# ESP32botV1.net
KiCad netlist of a schematic drawn in EAGLE
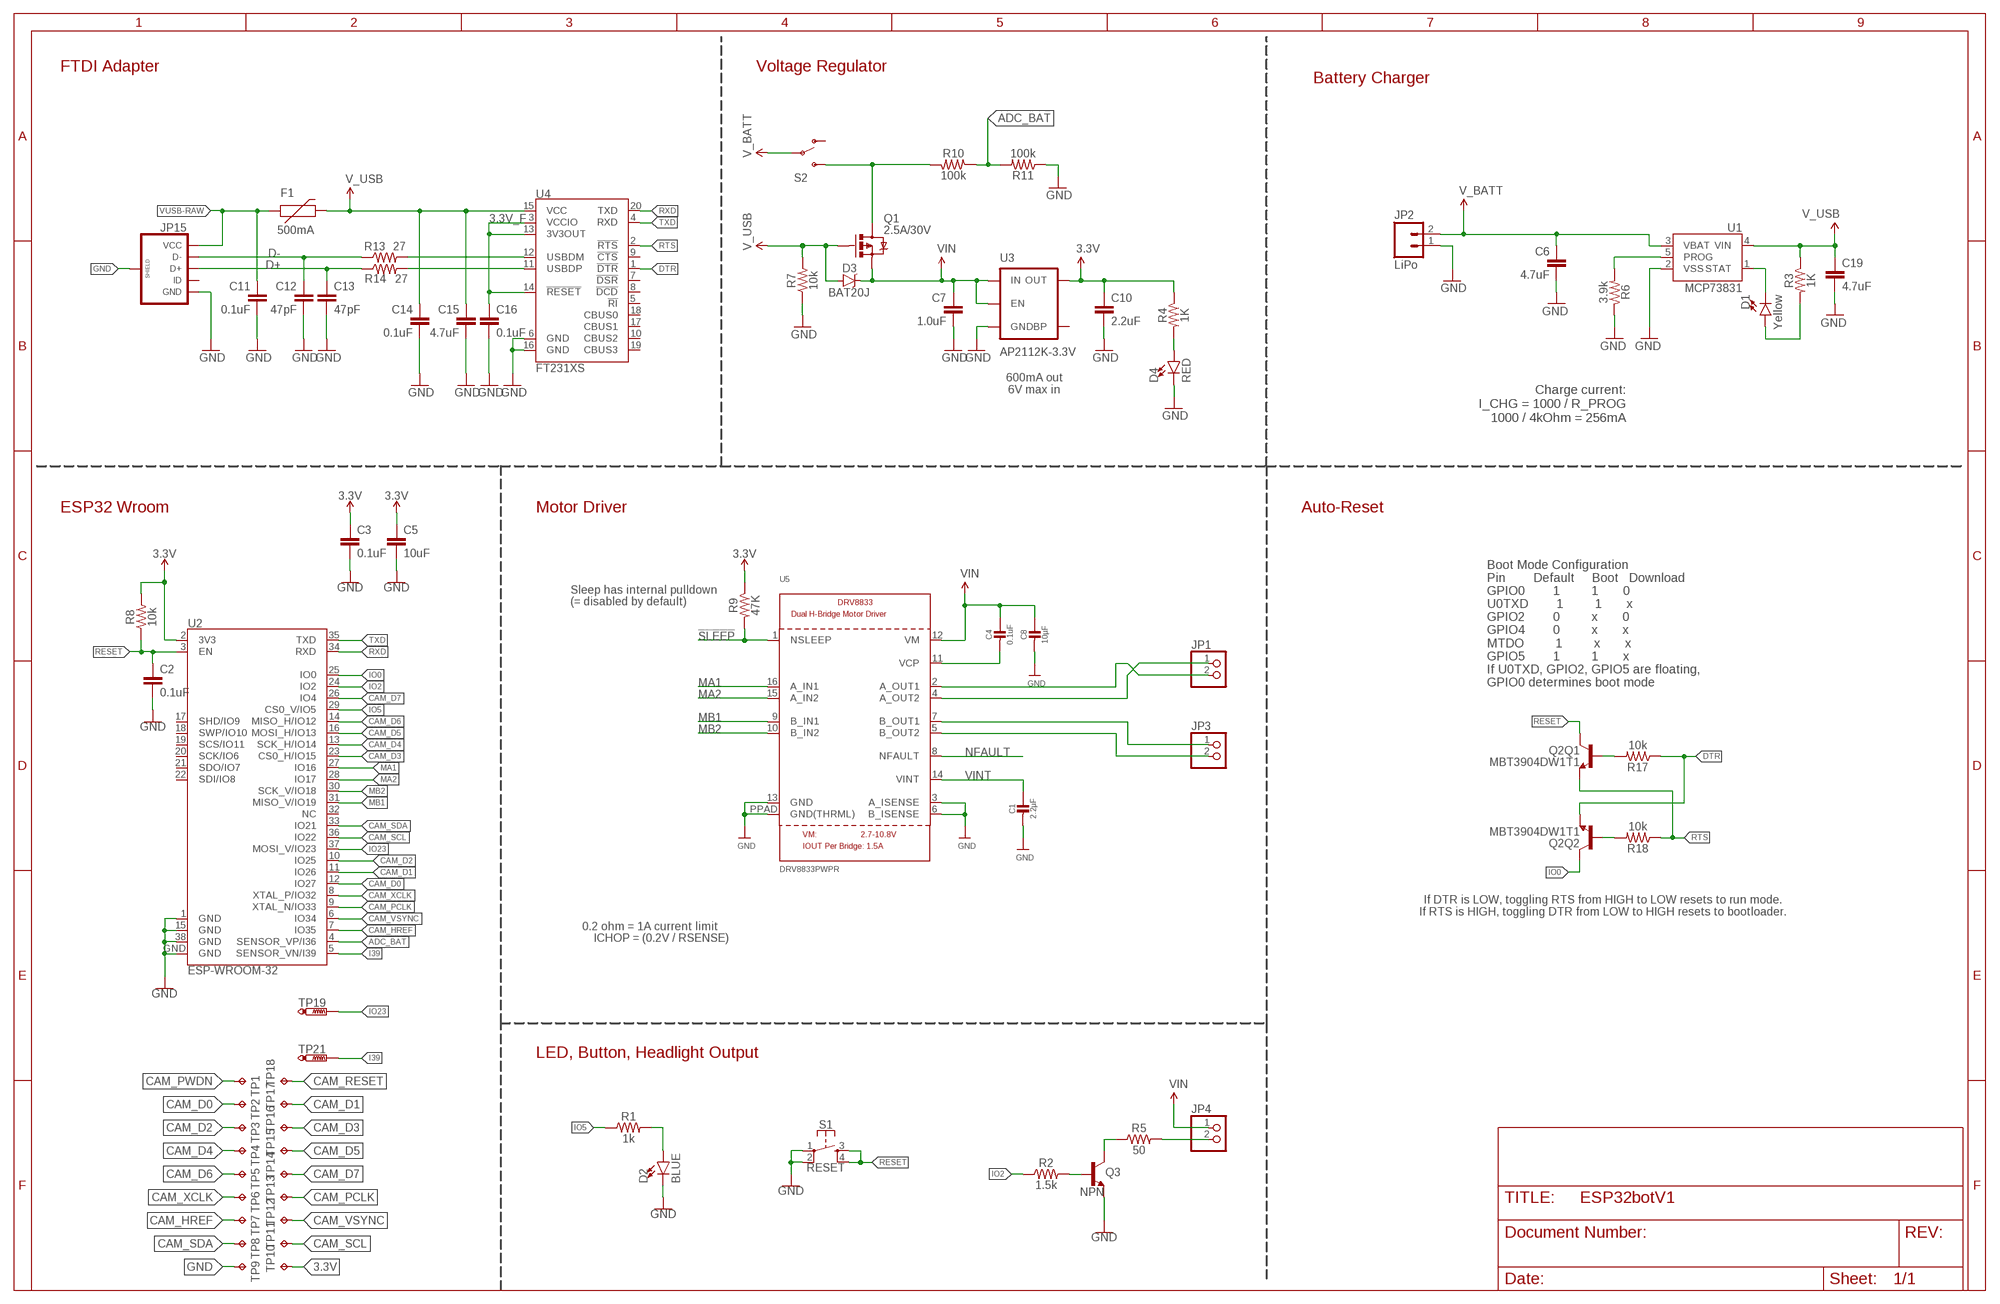
[diagram p0: schematic, sheet 1]

(export (version "E")
  (design (tool "Eeschema 10.0.6"))
  (components
    (comp (ref "C1")
      (value "2.2µF")
      (footprint "eagle-import:0805-NO")
      (libsource (lib "eagle-import") (part "CAP_CERAMIC0805-NOOUTLINE"))
    )
    (comp (ref "C2")
      (value "0.1uF")
      (footprint "eagle-import:0603")
      (libsource (lib "eagle-import") (part "0.1UF-0603-25V-(+80/-20%)"))
    )
    (comp (ref "C3")
      (value "0.1uF")
      (footprint "eagle-import:0603")
      (libsource (lib "eagle-import") (part "0.1UF-0603-25V-(+80/-20%)"))
    )
    (comp (ref "C4")
      (value "0.1uF")
      (footprint "eagle-import:0805-NO")
      (libsource (lib "eagle-import") (part "CAP_CERAMIC0805-NOOUTLINE"))
    )
    (comp (ref "C5")
      (value "10uF")
      (footprint "eagle-import:0603")
      (libsource (lib "eagle-import") (part "10UF-0603-6.3V-20%"))
    )
    (comp (ref "C6")
      (value "4.7uF")
      (footprint "eagle-import:0603")
      (libsource (lib "eagle-import") (part "4.7UF0603"))
    )
    (comp (ref "C7")
      (value "1.0uF")
      (footprint "eagle-import:0805")
      (libsource (lib "eagle-import") (part "1.0UF-0805-25V-(+80/-20%)"))
    )
    (comp (ref "C8")
      (value "10µF")
      (footprint "eagle-import:0805-NO")
      (libsource (lib "eagle-import") (part "CAP_CERAMIC0805-NOOUTLINE"))
    )
    (comp (ref "C10")
      (value "2.2uF")
      (footprint "eagle-import:0603")
      (libsource (lib "eagle-import") (part "2.2UF-0603-10V-20%"))
    )
    (comp (ref "C11")
      (value "0.1uF")
      (footprint "eagle-import:0603")
      (libsource (lib "eagle-import") (part "0.1UF-0603-25V-(+80/-20%)"))
    )
    (comp (ref "C12")
      (value "47pF")
      (footprint "eagle-import:0603")
      (libsource (lib "eagle-import") (part "47PF-0603-50V-5%"))
    )
    (comp (ref "C13")
      (value "47pF")
      (footprint "eagle-import:0603")
      (libsource (lib "eagle-import") (part "47PF-0603-50V-5%"))
    )
    (comp (ref "C14")
      (value "0.1uF")
      (footprint "eagle-import:0603")
      (libsource (lib "eagle-import") (part "0.1UF-0603-25V-(+80/-20%)"))
    )
    (comp (ref "C15")
      (value "4.7uF")
      (footprint "eagle-import:0603-CAP")
      (libsource (lib "eagle-import") (part "4.7UF-6.3V-10%(0603)0603"))
    )
    (comp (ref "C16")
      (value "0.1uF")
      (footprint "eagle-import:0603")
      (libsource (lib "eagle-import") (part "0.1UF-0603-25V-(+80/-20%)"))
    )
    (comp (ref "C19")
      (value "4.7uF")
      (footprint "eagle-import:0603")
      (libsource (lib "eagle-import") (part "4.7UF0603"))
    )
    (comp (ref "D1")
      (value "Yellow")
      (footprint "eagle-import:LED-0603@1")
      (libsource (lib "eagle-import") (part "LED-YELLOW0603"))
    )
    (comp (ref "D2")
      (value "BLUE")
      (footprint "eagle-import:LED-0603@2")
      (libsource (lib "eagle-import") (part "LED-BLUE0603"))
    )
    (comp (ref "D3")
      (value "BAT20J")
      (footprint "eagle-import:SOD-323")
      (libsource (lib "eagle-import") (part "DIODE-SCHOTTKY-BAT20J"))
    )
    (comp (ref "D4")
      (value "RED")
      (footprint "eagle-import:LED-0603")
      (libsource (lib "eagle-import") (part "LED-RED0603"))
    )
    (comp (ref "F1")
      (value "500mA")
      (footprint "eagle-import:PTC-1206")
      (libsource (lib "eagle-import") (part "PTCSMD"))
    )
    (comp (ref "JP1")
      (value "HEADER-1X2ROUND")
      (footprint "eagle-import:1X02_ROUND")
      (libsource (lib "eagle-import") (part "HEADER-1X2ROUND"))
    )
    (comp (ref "JP2")
      (value "LiPo")
      (footprint "eagle-import:JST-2-PTH")
      (libsource (lib "eagle-import") (part "M02JST-PTH-2"))
    )
    (comp (ref "JP3")
      (value "HEADER-1X2ROUND")
      (footprint "eagle-import:1X02_ROUND")
      (libsource (lib "eagle-import") (part "HEADER-1X2ROUND"))
    )
    (comp (ref "JP4")
      (value "HEADER-1X2ROUND")
      (footprint "eagle-import:1X02_ROUND")
      (libsource (lib "eagle-import") (part "HEADER-1X2ROUND"))
    )
    (comp (ref "JP15")
      (value "USB_MICROB_PLUGCONN-11752")
      (footprint "eagle-import:USB-B-MICRO-SMD_V03")
      (libsource (lib "eagle-import") (part "USB_MICROB_PLUGCONN-11752"))
    )
    (comp (ref "Q1")
      (value "2.5A/30V")
      (footprint "eagle-import:SOT23-3")
      (libsource (lib "eagle-import") (part "MOSFET-PCHANNELDMG2307L"))
    )
    (comp (ref "Q2")
      (value "MBT3904DW1T1")
      (footprint "eagle-import:SC70-6")
      (libsource (lib "eagle-import") (part "MBT3904DW1T1"))
    )
    (comp (ref "Q3")
      (value "NPN")
      (footprint "eagle-import:SOT23-3")
      (libsource (lib "eagle-import") (part "TRANSISTOR_NPNMMBT2222A"))
    )
    (comp (ref "R1")
      (value "1k")
      (footprint "eagle-import:0603")
      (libsource (lib "eagle-import") (part "1KOHM-0603-1/10W-1%"))
    )
    (comp (ref "R2")
      (value "1.5k")
      (footprint "eagle-import:0603")
      (libsource (lib "eagle-import") (part "1KOHM-0603-1/10W-1%"))
    )
    (comp (ref "R3")
      (value "1K")
      (footprint "eagle-import:0603")
      (libsource (lib "eagle-import") (part "1KOHM-1/10W-1%(0603)"))
    )
    (comp (ref "R4")
      (value "1K")
      (footprint "eagle-import:0603")
      (libsource (lib "eagle-import") (part "1KOHM-1/10W-1%(0603)"))
    )
    (comp (ref "R5")
      (value "50")
      (footprint "eagle-import:0603")
      (libsource (lib "eagle-import") (part "1KOHM-0603-1/10W-1%"))
    )
    (comp (ref "R6")
      (value "3.9k")
      (footprint "eagle-import:0603")
      (libsource (lib "eagle-import") (part "2.0KOHM1/10W5%(0603)"))
    )
    (comp (ref "R7")
      (value "10k")
      (footprint "eagle-import:0603")
      (libsource (lib "eagle-import") (part "10KOHM-0603-1/10W-1%"))
    )
    (comp (ref "R8")
      (value "10k")
      (footprint "eagle-import:0603")
      (libsource (lib "eagle-import") (part "10KOHM-0603-1/10W-1%"))
    )
    (comp (ref "R9")
      (value "47K")
      (footprint "eagle-import:0603")
      (libsource (lib "eagle-import") (part "1KOHM-1/10W-1%(0603)"))
    )
    (comp (ref "R10")
      (value "100k")
      (footprint "eagle-import:0603")
      (libsource (lib "eagle-import") (part "10KOHM-0603-1/10W-1%"))
    )
    (comp (ref "R11")
      (value "100k")
      (footprint "eagle-import:0603")
      (libsource (lib "eagle-import") (part "10KOHM-0603-1/10W-1%"))
    )
    (comp (ref "R13")
      (value "27")
      (footprint "eagle-import:0603")
      (libsource (lib "eagle-import") (part "27OHM1/10W1%(0603)0603-RES"))
    )
    (comp (ref "R14")
      (value "27")
      (footprint "eagle-import:0603")
      (libsource (lib "eagle-import") (part "27OHM1/10W1%(0603)0603-RES"))
    )
    (comp (ref "R17")
      (value "10k")
      (footprint "eagle-import:0603")
      (libsource (lib "eagle-import") (part "10KOHM-0603-1/10W-1%"))
    )
    (comp (ref "R18")
      (value "10k")
      (footprint "eagle-import:0603")
      (libsource (lib "eagle-import") (part "10KOHM-0603-1/10W-1%"))
    )
    (comp (ref "S1")
      (value "RESET")
      (footprint "eagle-import:TACTILE_SWITCH_SMD_4.6X2.8MM")
      (libsource (lib "eagle-import") (part "MOMENTARY-SWITCH-SPST-2-SMD-4.6X2.8MM"))
    )
    (comp (ref "S2")
      (value "SWITCH-SPDT-SMD-A")
      (footprint "eagle-import:SWITCH-SPST-SMD-A")
      (libsource (lib "eagle-import") (part "SWITCH-SPDT-SMD-A"))
    )
    (comp (ref "TP1")
      (value "TPEC")
      (footprint "eagle-import:EDGECONNECTOR")
      (libsource (lib "eagle-import") (part "TPEC"))
    )
    (comp (ref "TP2")
      (value "TPEC")
      (footprint "eagle-import:EDGECONNECTOR")
      (libsource (lib "eagle-import") (part "TPEC"))
    )
    (comp (ref "TP3")
      (value "TPEC")
      (footprint "eagle-import:EDGECONNECTOR")
      (libsource (lib "eagle-import") (part "TPEC"))
    )
    (comp (ref "TP4")
      (value "TPEC")
      (footprint "eagle-import:EDGECONNECTOR")
      (libsource (lib "eagle-import") (part "TPEC"))
    )
    (comp (ref "TP5")
      (value "TPEC")
      (footprint "eagle-import:EDGECONNECTOR")
      (libsource (lib "eagle-import") (part "TPEC"))
    )
    (comp (ref "TP6")
      (value "TPEC")
      (footprint "eagle-import:EDGECONNECTOR")
      (libsource (lib "eagle-import") (part "TPEC"))
    )
    (comp (ref "TP7")
      (value "TPEC")
      (footprint "eagle-import:EDGECONNECTOR")
      (libsource (lib "eagle-import") (part "TPEC"))
    )
    (comp (ref "TP8")
      (value "TPEC")
      (footprint "eagle-import:EDGECONNECTOR")
      (libsource (lib "eagle-import") (part "TPEC"))
    )
    (comp (ref "TP9")
      (value "TPEC")
      (footprint "eagle-import:EDGECONNECTOR")
      (libsource (lib "eagle-import") (part "TPEC"))
    )
    (comp (ref "TP10")
      (value "TPEC")
      (footprint "eagle-import:EDGECONNECTOR")
      (libsource (lib "eagle-import") (part "TPEC"))
    )
    (comp (ref "TP11")
      (value "TPEC")
      (footprint "eagle-import:EDGECONNECTOR")
      (libsource (lib "eagle-import") (part "TPEC"))
    )
    (comp (ref "TP12")
      (value "TPEC")
      (footprint "eagle-import:EDGECONNECTOR")
      (libsource (lib "eagle-import") (part "TPEC"))
    )
    (comp (ref "TP13")
      (value "TPEC")
      (footprint "eagle-import:EDGECONNECTOR")
      (libsource (lib "eagle-import") (part "TPEC"))
    )
    (comp (ref "TP14")
      (value "TPEC")
      (footprint "eagle-import:EDGECONNECTOR")
      (libsource (lib "eagle-import") (part "TPEC"))
    )
    (comp (ref "TP15")
      (value "TPEC")
      (footprint "eagle-import:EDGECONNECTOR")
      (libsource (lib "eagle-import") (part "TPEC"))
    )
    (comp (ref "TP16")
      (value "TPEC")
      (footprint "eagle-import:EDGECONNECTOR")
      (libsource (lib "eagle-import") (part "TPEC"))
    )
    (comp (ref "TP17")
      (value "TPEC")
      (footprint "eagle-import:EDGECONNECTOR")
      (libsource (lib "eagle-import") (part "TPEC"))
    )
    (comp (ref "TP18")
      (value "TPEC")
      (footprint "eagle-import:EDGECONNECTOR")
      (libsource (lib "eagle-import") (part "TPEC"))
    )
    (comp (ref "TP19")
      (value "PTR1TP13R")
      (footprint "eagle-import:TP13R")
      (libsource (lib "eagle-import") (part "PTR1TP13R"))
    )
    (comp (ref "TP21")
      (value "PTR1TP13R")
      (footprint "eagle-import:TP13R")
      (libsource (lib "eagle-import") (part "PTR1TP13R"))
    )
    (comp (ref "U1")
      (value "MCP73831")
      (footprint "eagle-import:SOT23-5")
      (libsource (lib "eagle-import") (part "MCP73831"))
    )
    (comp (ref "U2")
      (value "ESP-WROOM-32")
      (footprint "eagle-import:ESP-WROOM-32")
      (libsource (lib "eagle-import") (part "ESP-WROOM-32"))
    )
    (comp (ref "U3")
      (value "AP2112K-3.3V")
      (footprint "eagle-import:SOT23-5")
      (libsource (lib "eagle-import") (part "V_REG_LDOSMD"))
    )
    (comp (ref "U4")
      (value "FT231XS")
      (footprint "eagle-import:SSOP20_L")
      (libsource (lib "eagle-import") (part "FT231XS"))
    )
    (comp (ref "U5")
      (value "DRV8833PWPR")
      (footprint "eagle-import:HTSSOP16")
      (libsource (lib "eagle-import") (part "DRV8833"))
    )
  )
  (nets
    (net (code "1") (name "/3.3V_F") (class "Default")
      (node (ref "C16") (pin "1") (pinfunction "1_1") (pintype "passive"))
      (node (ref "U4") (pin "13") (pinfunction "3V3OUT_13") (pintype "bidirectional"))
      (node (ref "U4") (pin "14") (pinfunction "~{RESET}_14") (pintype "bidirectional"))
      (node (ref "U4") (pin "3") (pinfunction "VCCIO_3") (pintype "bidirectional"))
    )
    (net (code "2") (name "/D+") (class "Default")
      (node (ref "C13") (pin "1") (pinfunction "1_1") (pintype "passive"))
      (node (ref "JP15") (pin "D+") (pinfunction "D+_D+") (pintype "bidirectional"))
      (node (ref "R14") (pin "1") (pinfunction "1_1") (pintype "passive"))
    )
    (net (code "3") (name "/D-") (class "Default")
      (node (ref "C12") (pin "1") (pinfunction "1_1") (pintype "passive"))
      (node (ref "JP15") (pin "D-") (pinfunction "D-_D-") (pintype "bidirectional"))
      (node (ref "R13") (pin "1") (pinfunction "1_1") (pintype "passive"))
    )
    (net (code "4") (name "/NFAULT") (class "Default")
      (node (ref "U5") (pin "8") (pinfunction "NFAULT_8") (pintype "bidirectional"))
    )
    (net (code "5") (name "/VINT") (class "Default")
      (node (ref "C1") (pin "1") (pinfunction "1_1") (pintype "passive"))
      (node (ref "U5") (pin "14") (pinfunction "VINT_14") (pintype "power_in"))
    )
    (net (code "6") (name "/~{SLEEP}") (class "Default")
      (node (ref "R9") (pin "2") (pinfunction "2_2") (pintype "passive"))
      (node (ref "U5") (pin "1") (pinfunction "NSLEEP_1") (pintype "input"))
    )
    (net (code "7") (name "3.3V") (class "Default")
      (node (ref "C10") (pin "1") (pinfunction "1_1") (pintype "passive"))
      (node (ref "C3") (pin "1") (pinfunction "1_1") (pintype "passive"))
      (node (ref "C5") (pin "1") (pinfunction "1_1") (pintype "passive"))
      (node (ref "R4") (pin "1") (pinfunction "1_1") (pintype "passive"))
      (node (ref "R8") (pin "2") (pinfunction "2_2") (pintype "passive"))
      (node (ref "R9") (pin "1") (pinfunction "1_1") (pintype "passive"))
      (node (ref "TP10") (pin "TP") (pinfunction "TP_TP") (pintype "input"))
      (node (ref "U2") (pin "2") (pinfunction "3V3_2") (pintype "bidirectional"))
      (node (ref "U3") (pin "5") (pinfunction "OUT_5") (pintype "passive"))
    )
    (net (code "8") (name "ADC_BAT") (class "Default")
      (node (ref "R10") (pin "1") (pinfunction "1_1") (pintype "passive"))
      (node (ref "R11") (pin "2") (pinfunction "2_2") (pintype "passive"))
      (node (ref "U2") (pin "4") (pinfunction "SENSOR_VP/I36_4") (pintype "bidirectional"))
    )
    (net (code "9") (name "CAM_D0") (class "Default")
      (node (ref "TP2") (pin "TP") (pinfunction "TP_TP") (pintype "input"))
      (node (ref "U2") (pin "12") (pinfunction "IO27_12") (pintype "bidirectional"))
    )
    (net (code "10") (name "CAM_D1") (class "Default")
      (node (ref "TP17") (pin "TP") (pinfunction "TP_TP") (pintype "input"))
      (node (ref "U2") (pin "11") (pinfunction "IO26_11") (pintype "bidirectional"))
    )
    (net (code "11") (name "CAM_D2") (class "Default")
      (node (ref "TP3") (pin "TP") (pinfunction "TP_TP") (pintype "input"))
      (node (ref "U2") (pin "10") (pinfunction "IO25_10") (pintype "bidirectional"))
    )
    (net (code "12") (name "CAM_D3") (class "Default")
      (node (ref "TP16") (pin "TP") (pinfunction "TP_TP") (pintype "input"))
      (node (ref "U2") (pin "23") (pinfunction "CS0_H/IO15_23") (pintype "bidirectional"))
    )
    (net (code "13") (name "CAM_D4") (class "Default")
      (node (ref "TP4") (pin "TP") (pinfunction "TP_TP") (pintype "input"))
      (node (ref "U2") (pin "13") (pinfunction "SCK_H/IO14_13") (pintype "bidirectional"))
    )
    (net (code "14") (name "CAM_D5") (class "Default")
      (node (ref "TP15") (pin "TP") (pinfunction "TP_TP") (pintype "input"))
      (node (ref "U2") (pin "16") (pinfunction "MOSI_H/IO13_16") (pintype "bidirectional"))
    )
    (net (code "15") (name "CAM_D6") (class "Default")
      (node (ref "TP5") (pin "TP") (pinfunction "TP_TP") (pintype "input"))
      (node (ref "U2") (pin "14") (pinfunction "MISO_H/IO12_14") (pintype "bidirectional"))
    )
    (net (code "16") (name "CAM_D7") (class "Default")
      (node (ref "TP14") (pin "TP") (pinfunction "TP_TP") (pintype "input"))
      (node (ref "U2") (pin "26") (pinfunction "IO4_26") (pintype "bidirectional"))
    )
    (net (code "17") (name "CAM_HREF") (class "Default")
      (node (ref "TP7") (pin "TP") (pinfunction "TP_TP") (pintype "input"))
      (node (ref "U2") (pin "7") (pinfunction "IO35_7") (pintype "bidirectional"))
    )
    (net (code "18") (name "CAM_PCLK") (class "Default")
      (node (ref "TP13") (pin "TP") (pinfunction "TP_TP") (pintype "input"))
      (node (ref "U2") (pin "9") (pinfunction "XTAL_N/IO33_9") (pintype "bidirectional"))
    )
    (net (code "19") (name "CAM_PWDN") (class "Default")
      (node (ref "TP1") (pin "TP") (pinfunction "TP_TP") (pintype "input"))
    )
    (net (code "20") (name "CAM_RESET") (class "Default")
      (node (ref "TP18") (pin "TP") (pinfunction "TP_TP") (pintype "input"))
    )
    (net (code "21") (name "CAM_SCL") (class "Default")
      (node (ref "TP11") (pin "TP") (pinfunction "TP_TP") (pintype "input"))
      (node (ref "U2") (pin "36") (pinfunction "IO22_36") (pintype "bidirectional"))
    )
    (net (code "22") (name "CAM_SDA") (class "Default")
      (node (ref "TP8") (pin "TP") (pinfunction "TP_TP") (pintype "input"))
      (node (ref "U2") (pin "33") (pinfunction "IO21_33") (pintype "bidirectional"))
    )
    (net (code "23") (name "CAM_VSYNC") (class "Default")
      (node (ref "TP12") (pin "TP") (pinfunction "TP_TP") (pintype "input"))
      (node (ref "U2") (pin "6") (pinfunction "IO34_6") (pintype "bidirectional"))
    )
    (net (code "24") (name "CAM_XCLK") (class "Default")
      (node (ref "TP6") (pin "TP") (pinfunction "TP_TP") (pintype "input"))
      (node (ref "U2") (pin "8") (pinfunction "XTAL_P/IO32_8") (pintype "bidirectional"))
    )
    (net (code "25") (name "DTR") (class "Default")
      (node (ref "Q2") (pin "1") (pinfunction "E_1") (pintype "passive"))
      (node (ref "R17") (pin "1") (pinfunction "1_1") (pintype "passive"))
      (node (ref "U4") (pin "1") (pinfunction "~{DTR}_1") (pintype "bidirectional"))
    )
    (net (code "26") (name "GND") (class "Default")
      (node (ref "C1") (pin "2") (pinfunction "2_2") (pintype "passive"))
      (node (ref "C10") (pin "2") (pinfunction "2_2") (pintype "passive"))
      (node (ref "C11") (pin "2") (pinfunction "2_2") (pintype "passive"))
      (node (ref "C12") (pin "2") (pinfunction "2_2") (pintype "passive"))
      (node (ref "C13") (pin "2") (pinfunction "2_2") (pintype "passive"))
      (node (ref "C14") (pin "2") (pinfunction "2_2") (pintype "passive"))
      (node (ref "C15") (pin "2") (pinfunction "2_2") (pintype "passive"))
      (node (ref "C16") (pin "2") (pinfunction "2_2") (pintype "passive"))
      (node (ref "C19") (pin "2") (pinfunction "2_2") (pintype "passive"))
      (node (ref "C2") (pin "2") (pinfunction "2_2") (pintype "passive"))
      (node (ref "C3") (pin "2") (pinfunction "2_2") (pintype "passive"))
      (node (ref "C5") (pin "2") (pinfunction "2_2") (pintype "passive"))
      (node (ref "C6") (pin "2") (pinfunction "2_2") (pintype "passive"))
      (node (ref "C7") (pin "2") (pinfunction "2_2") (pintype "passive"))
      (node (ref "C8") (pin "2") (pinfunction "2_2") (pintype "passive"))
      (node (ref "D2") (pin "C") (pinfunction "C_C") (pintype "passive"))
      (node (ref "D4") (pin "C") (pinfunction "C_C") (pintype "passive"))
      (node (ref "JP15") (pin "GND") (pinfunction "GND_GND") (pintype "bidirectional"))
      (node (ref "JP15") (pin "SHIELD1") (pinfunction "SHIELD_SHIELD1") (pintype "bidirectional"))
      (node (ref "JP15") (pin "SHIELD2") (pinfunction "SHIELD_SHIELD2") (pintype "bidirectional"))
      (node (ref "JP15") (pin "SHIELD3") (pinfunction "SHIELD_SHIELD3") (pintype "bidirectional"))
      (node (ref "JP2") (pin "1") (pinfunction "1_1") (pintype "passive"))
      (node (ref "Q3") (pin "2") (pinfunction "E_2") (pintype "passive"))
      (node (ref "R11") (pin "1") (pinfunction "1_1") (pintype "passive"))
      (node (ref "R6") (pin "1") (pinfunction "1_1") (pintype "passive"))
      (node (ref "R7") (pin "1") (pinfunction "1_1") (pintype "passive"))
      (node (ref "S1") (pin "1") (pinfunction "1_1") (pintype "passive"))
      (node (ref "S1") (pin "2") (pinfunction "2_2") (pintype "passive"))
      (node (ref "TP9") (pin "TP") (pinfunction "TP_TP") (pintype "input"))
      (node (ref "U1") (pin "2") (pinfunction "VSS_2") (pintype "power_in"))
      (node (ref "U2") (pin "1") (pinfunction "GND_1") (pintype "bidirectional"))
      (node (ref "U2") (pin "15") (pinfunction "GND_15") (pintype "bidirectional"))
      (node (ref "U2") (pin "38") (pinfunction "GND_38") (pintype "bidirectional"))
      (node (ref "U2") (pin "GND") (pinfunction "GND_GND") (pintype "bidirectional"))
      (node (ref "U3") (pin "2") (pinfunction "GND_2") (pintype "input"))
      (node (ref "U4") (pin "16") (pinfunction "GND_16") (pintype "bidirectional"))
      (node (ref "U4") (pin "6") (pinfunction "GND_6") (pintype "bidirectional"))
      (node (ref "U5") (pin "13") (pinfunction "GND_13") (pintype "power_in"))
      (node (ref "U5") (pin "3") (pinfunction "A_ISENSE_3") (pintype "bidirectional"))
      (node (ref "U5") (pin "6") (pinfunction "B_ISENSE_6") (pintype "bidirectional"))
      (node (ref "U5") (pin "PPAD") (pinfunction "GND(THRML)_PPAD") (pintype "power_in"))
    )
    (net (code "27") (name "I39") (class "Default")
      (node (ref "TP21") (pin "TP") (pinfunction "TP_TP") (pintype "input"))
      (node (ref "U2") (pin "5") (pinfunction "SENSOR_VN/I39_5") (pintype "bidirectional"))
    )
    (net (code "28") (name "IO0") (class "Default")
      (node (ref "Q2") (pin "6") (pinfunction "C_6") (pintype "passive"))
      (node (ref "U2") (pin "25") (pinfunction "IO0_25") (pintype "bidirectional"))
    )
    (net (code "29") (name "IO2") (class "Default")
      (node (ref "R2") (pin "1") (pinfunction "1_1") (pintype "passive"))
      (node (ref "U2") (pin "24") (pinfunction "IO2_24") (pintype "bidirectional"))
    )
    (net (code "30") (name "IO5") (class "Default")
      (node (ref "R1") (pin "1") (pinfunction "1_1") (pintype "passive"))
      (node (ref "U2") (pin "29") (pinfunction "CS0_V/IO5_29") (pintype "bidirectional"))
    )
    (net (code "31") (name "IO23") (class "Default")
      (node (ref "TP19") (pin "TP") (pinfunction "TP_TP") (pintype "input"))
      (node (ref "U2") (pin "37") (pinfunction "MOSI_V/IO23_37") (pintype "bidirectional"))
    )
    (net (code "32") (name "MA1") (class "Default")
      (node (ref "U2") (pin "27") (pinfunction "IO16_27") (pintype "bidirectional"))
      (node (ref "U5") (pin "16") (pinfunction "A_IN1_16") (pintype "input"))
    )
    (net (code "33") (name "MA2") (class "Default")
      (node (ref "U2") (pin "28") (pinfunction "IO17_28") (pintype "bidirectional"))
      (node (ref "U5") (pin "15") (pinfunction "A_IN2_15") (pintype "input"))
    )
    (net (code "34") (name "MB1") (class "Default")
      (node (ref "U2") (pin "31") (pinfunction "MISO_V/IO19_31") (pintype "bidirectional"))
      (node (ref "U5") (pin "9") (pinfunction "B_IN1_9") (pintype "input"))
    )
    (net (code "35") (name "MB2") (class "Default")
      (node (ref "U2") (pin "30") (pinfunction "SCK_V/IO18_30") (pintype "bidirectional"))
      (node (ref "U5") (pin "10") (pinfunction "B_IN2_10") (pintype "input"))
    )
    (net (code "36") (name "Net-(D1-PadA)") (class "Default")
      (node (ref "D1") (pin "A") (pinfunction "A_A") (pintype "passive"))
      (node (ref "R3") (pin "2") (pinfunction "2_2") (pintype "passive"))
    )
    (net (code "37") (name "Net-(D2-PadA)") (class "Default")
      (node (ref "D2") (pin "A") (pinfunction "A_A") (pintype "passive"))
      (node (ref "R1") (pin "2") (pinfunction "2_2") (pintype "passive"))
    )
    (net (code "38") (name "Net-(D4-PadA)") (class "Default")
      (node (ref "D4") (pin "A") (pinfunction "A_A") (pintype "passive"))
      (node (ref "R4") (pin "2") (pinfunction "2_2") (pintype "passive"))
    )
    (net (code "39") (name "Net-(JP4-Pad2)") (class "Default")
      (node (ref "JP4") (pin "2") (pinfunction "2_2") (pintype "passive"))
      (node (ref "R5") (pin "2") (pinfunction "2_2") (pintype "passive"))
    )
    (net (code "40") (name "Net-(Q1-D)") (class "Default")
      (node (ref "Q1") (pin "3") (pinfunction "D_3") (pintype "passive"))
      (node (ref "R10") (pin "2") (pinfunction "2_2") (pintype "passive"))
      (node (ref "S2") (pin "3") (pinfunction "S_3") (pintype "passive"))
    )
    (net (code "41") (name "Net-(Q2A-B)") (class "Default")
      (node (ref "Q2") (pin "5") (pinfunction "B_5") (pintype "passive"))
      (node (ref "R17") (pin "2") (pinfunction "2_2") (pintype "passive"))
    )
    (net (code "42") (name "Net-(Q2B-B)") (class "Default")
      (node (ref "Q2") (pin "2") (pinfunction "B_2") (pintype "passive"))
      (node (ref "R18") (pin "2") (pinfunction "2_2") (pintype "passive"))
    )
    (net (code "43") (name "Net-(Q3-B)") (class "Default")
      (node (ref "Q3") (pin "1") (pinfunction "B_1") (pintype "passive"))
      (node (ref "R2") (pin "2") (pinfunction "2_2") (pintype "passive"))
    )
    (net (code "44") (name "Net-(Q3-C)") (class "Default")
      (node (ref "Q3") (pin "3") (pinfunction "C_3") (pintype "passive"))
      (node (ref "R5") (pin "1") (pinfunction "1_1") (pintype "passive"))
    )
    (net (code "45") (name "Net-(U1-PROG)") (class "Default")
      (node (ref "R6") (pin "2") (pinfunction "2_2") (pintype "passive"))
      (node (ref "U1") (pin "5") (pinfunction "PROG_5") (pintype "input"))
    )
    (net (code "46") (name "Net-(U1-STAT)") (class "Default")
      (node (ref "D1") (pin "C") (pinfunction "C_C") (pintype "passive"))
      (node (ref "U1") (pin "1") (pinfunction "STAT_1") (pintype "output"))
    )
    (net (code "47") (name "Net-(U4-USBDM)") (class "Default")
      (node (ref "R13") (pin "2") (pinfunction "2_2") (pintype "passive"))
      (node (ref "U4") (pin "12") (pinfunction "USBDM_12") (pintype "bidirectional"))
    )
    (net (code "48") (name "Net-(U4-USBDP)") (class "Default")
      (node (ref "R14") (pin "2") (pinfunction "2_2") (pintype "passive"))
      (node (ref "U4") (pin "11") (pinfunction "USBDP_11") (pintype "bidirectional"))
    )
    (net (code "49") (name "Net-(U5-A_OUT1)") (class "Default")
      (node (ref "JP1") (pin "2") (pinfunction "2_2") (pintype "passive"))
      (node (ref "U5") (pin "2") (pinfunction "A_OUT1_2") (pintype "output"))
    )
    (net (code "50") (name "Net-(U5-A_OUT2)") (class "Default")
      (node (ref "JP1") (pin "1") (pinfunction "1_1") (pintype "passive"))
      (node (ref "U5") (pin "4") (pinfunction "A_OUT2_4") (pintype "output"))
    )
    (net (code "51") (name "Net-(U5-B_OUT1)") (class "Default")
      (node (ref "JP3") (pin "1") (pinfunction "1_1") (pintype "passive"))
      (node (ref "U5") (pin "7") (pinfunction "B_OUT1_7") (pintype "output"))
    )
    (net (code "52") (name "Net-(U5-B_OUT2)") (class "Default")
      (node (ref "JP3") (pin "2") (pinfunction "2_2") (pintype "passive"))
      (node (ref "U5") (pin "5") (pinfunction "B_OUT2_5") (pintype "output"))
    )
    (net (code "53") (name "Net-(U5-VCP)") (class "Default")
      (node (ref "C4") (pin "2") (pinfunction "2_2") (pintype "passive"))
      (node (ref "U5") (pin "11") (pinfunction "VCP_11") (pintype "bidirectional"))
    )
    (net (code "54") (name "RESET") (class "Default")
      (node (ref "C2") (pin "1") (pinfunction "1_1") (pintype "passive"))
      (node (ref "Q2") (pin "3") (pinfunction "C_3") (pintype "passive"))
      (node (ref "R8") (pin "1") (pinfunction "1_1") (pintype "passive"))
      (node (ref "S1") (pin "3") (pinfunction "3_3") (pintype "passive"))
      (node (ref "S1") (pin "4") (pinfunction "4_4") (pintype "passive"))
      (node (ref "U2") (pin "3") (pinfunction "EN_3") (pintype "bidirectional"))
    )
    (net (code "55") (name "RTS") (class "Default")
      (node (ref "Q2") (pin "4") (pinfunction "E_4") (pintype "passive"))
      (node (ref "R18") (pin "1") (pinfunction "1_1") (pintype "passive"))
      (node (ref "U4") (pin "2") (pinfunction "~{RTS}_2") (pintype "bidirectional"))
    )
    (net (code "56") (name "RXD") (class "Default")
      (node (ref "U2") (pin "34") (pinfunction "RXD_34") (pintype "bidirectional"))
      (node (ref "U4") (pin "20") (pinfunction "TXD_20") (pintype "bidirectional"))
    )
    (net (code "57") (name "TXD") (class "Default")
      (node (ref "U2") (pin "35") (pinfunction "TXD_35") (pintype "bidirectional"))
      (node (ref "U4") (pin "4") (pinfunction "RXD_4") (pintype "bidirectional"))
    )
    (net (code "58") (name "VIN") (class "Default")
      (node (ref "C4") (pin "1") (pinfunction "1_1") (pintype "passive"))
      (node (ref "C7") (pin "1") (pinfunction "1_1") (pintype "passive"))
      (node (ref "C8") (pin "1") (pinfunction "1_1") (pintype "passive"))
      (node (ref "D3") (pin "C") (pinfunction "C_C") (pintype "passive"))
      (node (ref "JP4") (pin "1") (pinfunction "1_1") (pintype "passive"))
      (node (ref "Q1") (pin "2") (pinfunction "S_2") (pintype "passive"))
      (node (ref "U3") (pin "1") (pinfunction "IN_1") (pintype "input"))
      (node (ref "U3") (pin "3") (pinfunction "EN_3") (pintype "input"))
      (node (ref "U5") (pin "12") (pinfunction "VM_12") (pintype "power_in"))
    )
    (net (code "59") (name "VUSB-RAW") (class "Default")
      (node (ref "C11") (pin "1") (pinfunction "1_1") (pintype "passive"))
      (node (ref "F1") (pin "1") (pinfunction "1_1") (pintype "bidirectional"))
      (node (ref "JP15") (pin "VBUS") (pinfunction "VCC_VBUS") (pintype "bidirectional"))
    )
    (net (code "60") (name "V_BATT") (class "Default")
      (node (ref "C6") (pin "1") (pinfunction "1_1") (pintype "passive"))
      (node (ref "JP2") (pin "2") (pinfunction "2_2") (pintype "passive"))
      (node (ref "S2") (pin "2") (pinfunction "P_2") (pintype "passive"))
      (node (ref "U1") (pin "3") (pinfunction "VBAT_3") (pintype "power_in"))
    )
    (net (code "61") (name "V_USB") (class "Default")
      (node (ref "C14") (pin "1") (pinfunction "1_1") (pintype "passive"))
      (node (ref "C15") (pin "1") (pinfunction "1_1") (pintype "passive"))
      (node (ref "C19") (pin "1") (pinfunction "1_1") (pintype "passive"))
      (node (ref "D3") (pin "A") (pinfunction "A_A") (pintype "passive"))
      (node (ref "F1") (pin "2") (pinfunction "2_2") (pintype "bidirectional"))
      (node (ref "Q1") (pin "1") (pinfunction "G_1") (pintype "passive"))
      (node (ref "R3") (pin "1") (pinfunction "1_1") (pintype "passive"))
      (node (ref "R7") (pin "2") (pinfunction "2_2") (pintype "passive"))
      (node (ref "U1") (pin "4") (pinfunction "VIN_4") (pintype "power_in"))
      (node (ref "U4") (pin "15") (pinfunction "VCC_15") (pintype "bidirectional"))
    )
    (net (code "62") (name "unconnected-(JP15-PadID)") (class "Default")
      (node (ref "JP15") (pin "ID") (pinfunction "ID_ID") (pintype "bidirectional"))
    )
    (net (code "63") (name "unconnected-(S2-O-Pad1)") (class "Default")
      (node (ref "S2") (pin "1") (pinfunction "O_1") (pintype "passive"))
    )
    (net (code "64") (name "unconnected-(U2-NC-Pad32)") (class "Default")
      (node (ref "U2") (pin "32") (pinfunction "NC_32") (pintype "bidirectional"))
    )
    (net (code "65") (name "unconnected-(U2-SCK{slash}IO6-Pad20)") (class "Default")
      (node (ref "U2") (pin "20") (pinfunction "SCK/IO6_20") (pintype "bidirectional"))
    )
    (net (code "66") (name "unconnected-(U2-SCS{slash}IO11-Pad19)") (class "Default")
      (node (ref "U2") (pin "19") (pinfunction "SCS/IO11_19") (pintype "bidirectional"))
    )
    (net (code "67") (name "unconnected-(U2-SDI{slash}IO8-Pad22)") (class "Default")
      (node (ref "U2") (pin "22") (pinfunction "SDI/IO8_22") (pintype "bidirectional"))
    )
    (net (code "68") (name "unconnected-(U2-SDO{slash}IO7-Pad21)") (class "Default")
      (node (ref "U2") (pin "21") (pinfunction "SDO/IO7_21") (pintype "bidirectional"))
    )
    (net (code "69") (name "unconnected-(U2-SHD{slash}IO9-Pad17)") (class "Default")
      (node (ref "U2") (pin "17") (pinfunction "SHD/IO9_17") (pintype "bidirectional"))
    )
    (net (code "70") (name "unconnected-(U2-SWP{slash}IO10-Pad18)") (class "Default")
      (node (ref "U2") (pin "18") (pinfunction "SWP/IO10_18") (pintype "bidirectional"))
    )
    (net (code "71") (name "unconnected-(U3-BP-Pad4)") (class "Default")
      (node (ref "U3") (pin "4") (pinfunction "BP_4") (pintype "input"))
    )
    (net (code "72") (name "unconnected-(U4-CBUS0-Pad18)") (class "Default")
      (node (ref "U4") (pin "18") (pinfunction "CBUS0_18") (pintype "bidirectional"))
    )
    (net (code "73") (name "unconnected-(U4-CBUS1-Pad17)") (class "Default")
      (node (ref "U4") (pin "17") (pinfunction "CBUS1_17") (pintype "bidirectional"))
    )
    (net (code "74") (name "unconnected-(U4-CBUS2-Pad10)") (class "Default")
      (node (ref "U4") (pin "10") (pinfunction "CBUS2_10") (pintype "bidirectional"))
    )
    (net (code "75") (name "unconnected-(U4-CBUS3-Pad19)") (class "Default")
      (node (ref "U4") (pin "19") (pinfunction "CBUS3_19") (pintype "bidirectional"))
    )
    (net (code "76") (name "unconnected-(U4-~{CTS}-Pad9)") (class "Default")
      (node (ref "U4") (pin "9") (pinfunction "~{CTS}_9") (pintype "bidirectional"))
    )
    (net (code "77") (name "unconnected-(U4-~{DCD}-Pad8)") (class "Default")
      (node (ref "U4") (pin "8") (pinfunction "~{DCD}_8") (pintype "bidirectional"))
    )
    (net (code "78") (name "unconnected-(U4-~{DSR}-Pad7)") (class "Default")
      (node (ref "U4") (pin "7") (pinfunction "~{DSR}_7") (pintype "bidirectional"))
    )
    (net (code "79") (name "unconnected-(U4-~{RI}-Pad5)") (class "Default")
      (node (ref "U4") (pin "5") (pinfunction "~{RI}_5") (pintype "bidirectional"))
    )
  )
)
